# 2CAN_Processor.net
KiCad netlist of a schematic drawn in Altium Designer
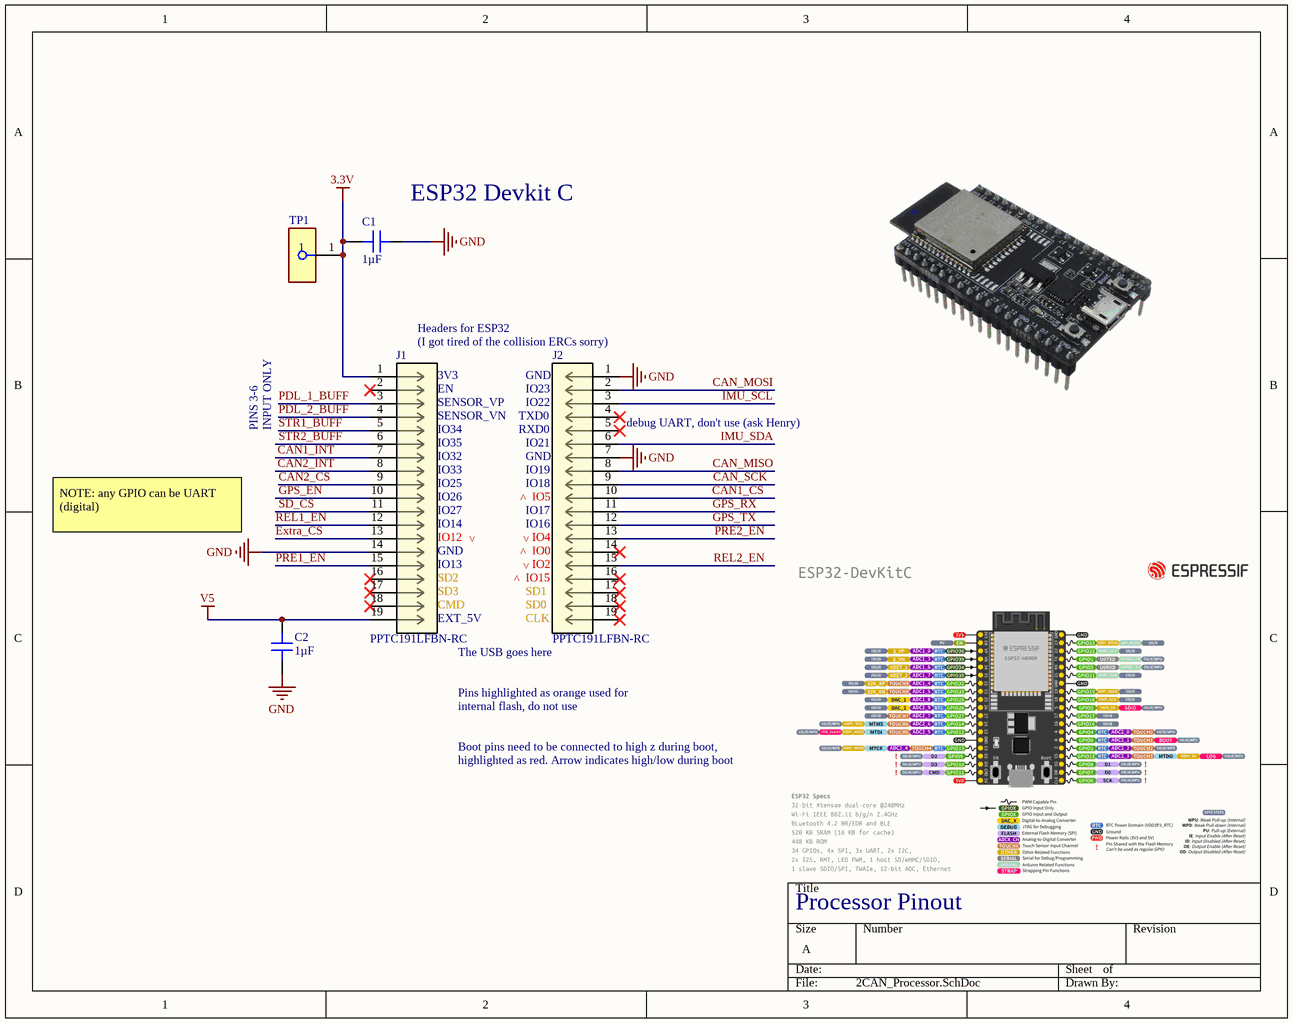
[diagram p0: 2CAN_Processor.SchDoc]

(export (version "E")
  (design (tool "Eeschema 10.0.6"))
  (components
    (comp (ref "C1")
      (value "1µF")
      (footprint "CAP 0603_1608")
      (description "CAP CER 1UF 25V X5R 0603")
      (fields (field (name "PART NUMBER") "06033D105MAT2A") (field (name "MANUFACTURER") "AVX Corporation"))
      (libsource (lib "Celestial Altium Library - altium_library") (part "Capacitor"))
    )
    (comp (ref "C2")
      (value "1µF")
      (footprint "CAP 0603_1608")
      (description "CAP CER 1UF 25V X5R 0603")
      (fields (field (name "PART NUMBER") "06033D105MAT2A") (field (name "MANUFACTURER") "AVX Corporation"))
      (libsource (lib "Celestial Altium Library - altium_library") (part "Capacitor"))
    )
    (comp (ref "J1")
      (value "PPTC191LFBN-RC")
      (footprint "CONN19_PPTC191LFBN-RC_SUL")
      (description "No Description Available")
      (fields (field (name "COPYRIGHT") "Copyright (C) 2023 Ultra Librarian. All rights reserved."))
      (libsource (lib "PPTC191LFBN-RC") (part "PPTC191LFBN-RC"))
    )
    (comp (ref "J2")
      (value "PPTC191LFBN-RC")
      (footprint "CONN19_PPTC191LFBN-RC_SUL")
      (description "No Description Available")
      (fields (field (name "COPYRIGHT") "Copyright (C) 2023 Ultra Librarian. All rights reserved."))
      (libsource (lib "PPTC191LFBN-RC") (part "PPTC191LFBN-RC"))
    )
    (comp (ref "TP1")
      (value "S2761-46R")
      (footprint "FP-S2761-46R-MFG")
      (description "PC TEST POINT NATURAL")
      (libsource (lib "Altium Content Vault") (part "98815daf2f2c152b0c43f5ab9800df6"))
    )
  )
  (nets
    (net (code "1") (name "/CAN1_CS") (class "Default")
      (node (ref "J2") (pin "10") (pinfunction "10_10") (pintype "passive"))
    )
    (net (code "2") (name "/CAN1_INT") (class "Default")
      (node (ref "J1") (pin "7") (pinfunction "7_7") (pintype "passive"))
    )
    (net (code "3") (name "/CAN2_CS") (class "Default")
      (node (ref "J1") (pin "9") (pinfunction "9_9") (pintype "passive"))
    )
    (net (code "4") (name "/CAN2_INT") (class "Default")
      (node (ref "J1") (pin "8") (pinfunction "8_8") (pintype "passive"))
    )
    (net (code "5") (name "/CAN_MISO") (class "Default")
      (node (ref "J2") (pin "8") (pinfunction "8_8") (pintype "passive"))
    )
    (net (code "6") (name "/CAN_MOSI") (class "Default")
      (node (ref "J2") (pin "2") (pinfunction "2_2") (pintype "passive"))
    )
    (net (code "7") (name "/CAN_SCK") (class "Default")
      (node (ref "J2") (pin "9") (pinfunction "9_9") (pintype "passive"))
    )
    (net (code "8") (name "/Extra_CS") (class "Default")
      (node (ref "J1") (pin "13") (pinfunction "13_13") (pintype "passive"))
    )
    (net (code "9") (name "/GPS_EN") (class "Default")
      (node (ref "J1") (pin "10") (pinfunction "10_10") (pintype "passive"))
    )
    (net (code "10") (name "/GPS_RX") (class "Default")
      (node (ref "J2") (pin "11") (pinfunction "11_11") (pintype "passive"))
    )
    (net (code "11") (name "/GPS_TX") (class "Default")
      (node (ref "J2") (pin "12") (pinfunction "12_12") (pintype "passive"))
    )
    (net (code "12") (name "/IMU_SCL") (class "Default")
      (node (ref "J2") (pin "3") (pinfunction "3_3") (pintype "passive"))
    )
    (net (code "13") (name "/IMU_SDA") (class "Default")
      (node (ref "J2") (pin "6") (pinfunction "6_6") (pintype "passive"))
    )
    (net (code "14") (name "/PDL_1_BUFF") (class "Default")
      (node (ref "J1") (pin "3") (pinfunction "3_3") (pintype "passive"))
    )
    (net (code "15") (name "/PDL_2_BUFF") (class "Default")
      (node (ref "J1") (pin "4") (pinfunction "4_4") (pintype "passive"))
    )
    (net (code "16") (name "/PRE1_EN") (class "Default")
      (node (ref "J1") (pin "15") (pinfunction "15_15") (pintype "passive"))
    )
    (net (code "17") (name "/PRE2_EN") (class "Default")
      (node (ref "J2") (pin "13") (pinfunction "13_13") (pintype "passive"))
    )
    (net (code "18") (name "/REL1_EN") (class "Default")
      (node (ref "J1") (pin "12") (pinfunction "12_12") (pintype "passive"))
    )
    (net (code "19") (name "/REL2_EN") (class "Default")
      (node (ref "J2") (pin "15") (pinfunction "15_15") (pintype "passive"))
    )
    (net (code "20") (name "/SD_CS") (class "Default")
      (node (ref "J1") (pin "11") (pinfunction "11_11") (pintype "passive"))
    )
    (net (code "21") (name "/STR1_BUFF") (class "Default")
      (node (ref "J1") (pin "5") (pinfunction "5_5") (pintype "passive"))
    )
    (net (code "22") (name "/STR2_BUFF") (class "Default")
      (node (ref "J1") (pin "6") (pinfunction "6_6") (pintype "passive"))
    )
    (net (code "23") (name "3.3V") (class "Default")
      (node (ref "C1") (pin "1") (pinfunction "1_1") (pintype "passive"))
      (node (ref "J1") (pin "1") (pinfunction "1_1") (pintype "passive"))
      (node (ref "TP1") (pin "1") (pinfunction "1_1") (pintype "passive"))
    )
    (net (code "24") (name "GND") (class "Default")
      (node (ref "C1") (pin "2") (pinfunction "2_2") (pintype "passive"))
      (node (ref "C2") (pin "1") (pinfunction "1_1") (pintype "passive"))
      (node (ref "J1") (pin "14") (pinfunction "14_14") (pintype "passive"))
      (node (ref "J2") (pin "1") (pinfunction "1_1") (pintype "passive"))
      (node (ref "J2") (pin "7") (pinfunction "7_7") (pintype "passive"))
    )
    (net (code "25") (name "V5") (class "Default")
      (node (ref "C2") (pin "2") (pinfunction "2_2") (pintype "passive"))
      (node (ref "J1") (pin "19") (pinfunction "19_19") (pintype "passive"))
    )
    (net (code "26") (name "unconnected-(J1-Pad2)") (class "Default")
      (node (ref "J1") (pin "2") (pinfunction "2_2") (pintype "passive+no_connect"))
    )
    (net (code "27") (name "unconnected-(J1-Pad16)") (class "Default")
      (node (ref "J1") (pin "16") (pinfunction "16_16") (pintype "passive+no_connect"))
    )
    (net (code "28") (name "unconnected-(J1-Pad17)") (class "Default")
      (node (ref "J1") (pin "17") (pinfunction "17_17") (pintype "passive+no_connect"))
    )
    (net (code "29") (name "unconnected-(J1-Pad18)") (class "Default")
      (node (ref "J1") (pin "18") (pinfunction "18_18") (pintype "passive+no_connect"))
    )
    (net (code "30") (name "unconnected-(J2-Pad4)") (class "Default")
      (node (ref "J2") (pin "4") (pinfunction "4_4") (pintype "passive+no_connect"))
    )
    (net (code "31") (name "unconnected-(J2-Pad5)") (class "Default")
      (node (ref "J2") (pin "5") (pinfunction "5_5") (pintype "passive+no_connect"))
    )
    (net (code "32") (name "unconnected-(J2-Pad14)") (class "Default")
      (node (ref "J2") (pin "14") (pinfunction "14_14") (pintype "passive+no_connect"))
    )
    (net (code "33") (name "unconnected-(J2-Pad16)") (class "Default")
      (node (ref "J2") (pin "16") (pinfunction "16_16") (pintype "passive+no_connect"))
    )
    (net (code "34") (name "unconnected-(J2-Pad17)") (class "Default")
      (node (ref "J2") (pin "17") (pinfunction "17_17") (pintype "passive+no_connect"))
    )
    (net (code "35") (name "unconnected-(J2-Pad18)") (class "Default")
      (node (ref "J2") (pin "18") (pinfunction "18_18") (pintype "passive+no_connect"))
    )
    (net (code "36") (name "unconnected-(J2-Pad19)") (class "Default")
      (node (ref "J2") (pin "19") (pinfunction "19_19") (pintype "passive+no_connect"))
    )
  )
)
